# untitled.net
KiCad netlist of a schematic drawn in EAGLE
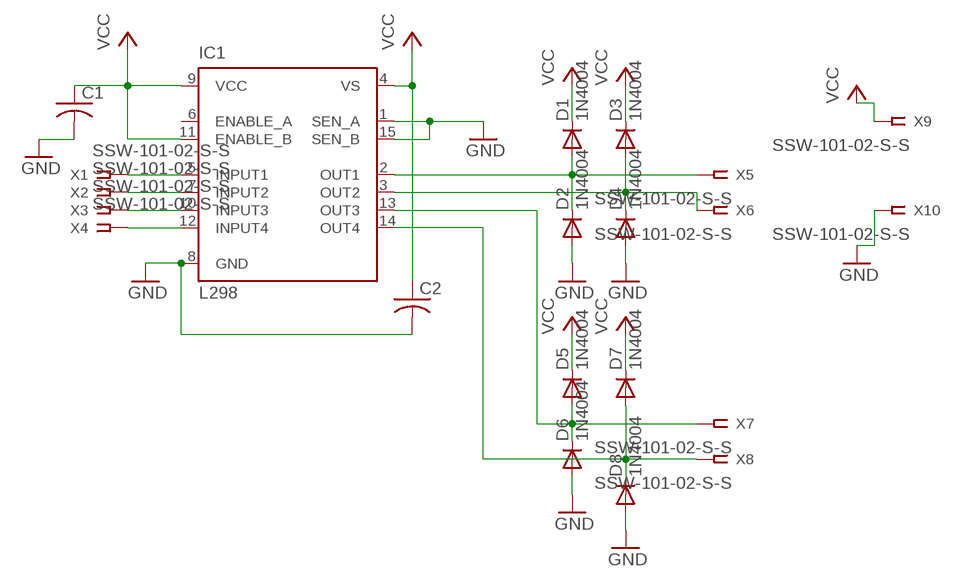
[diagram p0: schematic, sheet 1]

(export (version "E")
  (design (tool "Eeschema 10.0.6"))
  (components
    (comp (ref "C1")
      (value "C-US025-025X050")
      (footprint "eagle-import:C025-025X050")
      (libsource (lib "eagle-import") (part "C-US025-025X050"))
    )
    (comp (ref "C2")
      (value "C-US025-025X050")
      (footprint "eagle-import:C025-025X050")
      (libsource (lib "eagle-import") (part "C-US025-025X050"))
    )
    (comp (ref "D1")
      (value "1N4004")
      (footprint "eagle-import:DO41-10")
      (libsource (lib "eagle-import") (part "1N4004"))
    )
    (comp (ref "D2")
      (value "1N4004")
      (footprint "eagle-import:DO41-10")
      (libsource (lib "eagle-import") (part "1N4004"))
    )
    (comp (ref "D3")
      (value "1N4004")
      (footprint "eagle-import:DO41-10")
      (libsource (lib "eagle-import") (part "1N4004"))
    )
    (comp (ref "D4")
      (value "1N4004")
      (footprint "eagle-import:DO41-10")
      (libsource (lib "eagle-import") (part "1N4004"))
    )
    (comp (ref "D5")
      (value "1N4004")
      (footprint "eagle-import:DO41-10")
      (libsource (lib "eagle-import") (part "1N4004"))
    )
    (comp (ref "D6")
      (value "1N4004")
      (footprint "eagle-import:DO41-10")
      (libsource (lib "eagle-import") (part "1N4004"))
    )
    (comp (ref "D7")
      (value "1N4004")
      (footprint "eagle-import:DO41-10")
      (libsource (lib "eagle-import") (part "1N4004"))
    )
    (comp (ref "D8")
      (value "1N4004")
      (footprint "eagle-import:DO41-10")
      (libsource (lib "eagle-import") (part "1N4004"))
    )
    (comp (ref "IC1")
      (value "L298")
      (footprint "eagle-import:MULTIWATT-15")
      (fields (field (name "MPN") "L298N"))
      (libsource (lib "eagle-import") (part "L298"))
    )
    (comp (ref "X1")
      (value "SSW-101-02-S-S")
      (footprint "eagle-import:SSW-101-02-S-S")
      (libsource (lib "eagle-import") (part "SSW-101-02-S-S"))
    )
    (comp (ref "X2")
      (value "SSW-101-02-S-S")
      (footprint "eagle-import:SSW-101-02-S-S")
      (libsource (lib "eagle-import") (part "SSW-101-02-S-S"))
    )
    (comp (ref "X3")
      (value "SSW-101-02-S-S")
      (footprint "eagle-import:SSW-101-02-S-S")
      (libsource (lib "eagle-import") (part "SSW-101-02-S-S"))
    )
    (comp (ref "X4")
      (value "SSW-101-02-S-S")
      (footprint "eagle-import:SSW-101-02-S-S")
      (libsource (lib "eagle-import") (part "SSW-101-02-S-S"))
    )
    (comp (ref "X5")
      (value "SSW-101-02-S-S")
      (footprint "eagle-import:SSW-101-02-S-S")
      (libsource (lib "eagle-import") (part "SSW-101-02-S-S"))
    )
    (comp (ref "X6")
      (value "SSW-101-02-S-S")
      (footprint "eagle-import:SSW-101-02-S-S")
      (libsource (lib "eagle-import") (part "SSW-101-02-S-S"))
    )
    (comp (ref "X7")
      (value "SSW-101-02-S-S")
      (footprint "eagle-import:SSW-101-02-S-S")
      (libsource (lib "eagle-import") (part "SSW-101-02-S-S"))
    )
    (comp (ref "X8")
      (value "SSW-101-02-S-S")
      (footprint "eagle-import:SSW-101-02-S-S")
      (libsource (lib "eagle-import") (part "SSW-101-02-S-S"))
    )
    (comp (ref "X9")
      (value "SSW-101-02-S-S")
      (footprint "eagle-import:SSW-101-02-S-S")
      (libsource (lib "eagle-import") (part "SSW-101-02-S-S"))
    )
    (comp (ref "X10")
      (value "SSW-101-02-S-S")
      (footprint "eagle-import:SSW-101-02-S-S")
      (libsource (lib "eagle-import") (part "SSW-101-02-S-S"))
    )
  )
  (nets
    (net (code "1") (name "GND") (class "Default")
      (node (ref "C1") (pin "2") (pinfunction "2_2") (pintype "passive"))
      (node (ref "C2") (pin "2") (pinfunction "2_2") (pintype "passive"))
      (node (ref "D2") (pin "A") (pinfunction "A_A") (pintype "passive"))
      (node (ref "D4") (pin "A") (pinfunction "A_A") (pintype "passive"))
      (node (ref "D6") (pin "A") (pinfunction "A_A") (pintype "passive"))
      (node (ref "D8") (pin "A") (pinfunction "A_A") (pintype "passive"))
      (node (ref "IC1") (pin "1") (pinfunction "SEN_A_1") (pintype "input"))
      (node (ref "IC1") (pin "15") (pinfunction "SEN_B_15") (pintype "input"))
      (node (ref "IC1") (pin "8") (pinfunction "GND_8") (pintype "power_in"))
      (node (ref "X10") (pin "1") (pinfunction "1_1") (pintype "passive"))
    )
    (net (code "2") (name "Net-(IC1-INPUT1)") (class "Default")
      (node (ref "IC1") (pin "5") (pinfunction "INPUT1_5") (pintype "input"))
      (node (ref "X1") (pin "1") (pinfunction "1_1") (pintype "passive"))
    )
    (net (code "3") (name "Net-(IC1-INPUT2)") (class "Default")
      (node (ref "IC1") (pin "7") (pinfunction "INPUT2_7") (pintype "input"))
      (node (ref "X2") (pin "1") (pinfunction "1_1") (pintype "passive"))
    )
    (net (code "4") (name "Net-(IC1-INPUT3)") (class "Default")
      (node (ref "IC1") (pin "10") (pinfunction "INPUT3_10") (pintype "input"))
      (node (ref "X3") (pin "1") (pinfunction "1_1") (pintype "passive"))
    )
    (net (code "5") (name "Net-(IC1-INPUT4)") (class "Default")
      (node (ref "IC1") (pin "12") (pinfunction "INPUT4_12") (pintype "input"))
      (node (ref "X4") (pin "1") (pinfunction "1_1") (pintype "passive"))
    )
    (net (code "6") (name "Net-(IC1-OUT1)") (class "Default")
      (node (ref "D1") (pin "A") (pinfunction "A_A") (pintype "passive"))
      (node (ref "D2") (pin "C") (pinfunction "C_C") (pintype "passive"))
      (node (ref "IC1") (pin "2") (pinfunction "OUT1_2") (pintype "output"))
      (node (ref "X5") (pin "1") (pinfunction "1_1") (pintype "passive"))
    )
    (net (code "7") (name "Net-(IC1-OUT2)") (class "Default")
      (node (ref "D3") (pin "A") (pinfunction "A_A") (pintype "passive"))
      (node (ref "D4") (pin "C") (pinfunction "C_C") (pintype "passive"))
      (node (ref "IC1") (pin "3") (pinfunction "OUT2_3") (pintype "output"))
      (node (ref "X6") (pin "1") (pinfunction "1_1") (pintype "passive"))
    )
    (net (code "8") (name "Net-(IC1-OUT3)") (class "Default")
      (node (ref "D5") (pin "A") (pinfunction "A_A") (pintype "passive"))
      (node (ref "D6") (pin "C") (pinfunction "C_C") (pintype "passive"))
      (node (ref "IC1") (pin "13") (pinfunction "OUT3_13") (pintype "output"))
      (node (ref "X7") (pin "1") (pinfunction "1_1") (pintype "passive"))
    )
    (net (code "9") (name "Net-(IC1-OUT4)") (class "Default")
      (node (ref "D7") (pin "A") (pinfunction "A_A") (pintype "passive"))
      (node (ref "D8") (pin "C") (pinfunction "C_C") (pintype "passive"))
      (node (ref "IC1") (pin "14") (pinfunction "OUT4_14") (pintype "output"))
      (node (ref "X8") (pin "1") (pinfunction "1_1") (pintype "passive"))
    )
    (net (code "10") (name "VCC") (class "Default")
      (node (ref "C1") (pin "1") (pinfunction "1_1") (pintype "passive"))
      (node (ref "C2") (pin "1") (pinfunction "1_1") (pintype "passive"))
      (node (ref "D1") (pin "C") (pinfunction "C_C") (pintype "passive"))
      (node (ref "D3") (pin "C") (pinfunction "C_C") (pintype "passive"))
      (node (ref "D5") (pin "C") (pinfunction "C_C") (pintype "passive"))
      (node (ref "D7") (pin "C") (pinfunction "C_C") (pintype "passive"))
      (node (ref "IC1") (pin "11") (pinfunction "ENABLE_B_11") (pintype "input"))
      (node (ref "IC1") (pin "4") (pinfunction "VS_4") (pintype "power_in"))
      (node (ref "IC1") (pin "9") (pinfunction "VCC_9") (pintype "power_in"))
      (node (ref "X9") (pin "1") (pinfunction "1_1") (pintype "passive"))
    )
    (net (code "11") (name "unconnected-(IC1-ENABLE_A-Pad6)") (class "Default")
      (node (ref "IC1") (pin "6") (pinfunction "ENABLE_A_6") (pintype "input"))
    )
  )
)
